# preamp_module_mic_rev1.net
KiCad netlist of a schematic drawn in EAGLE
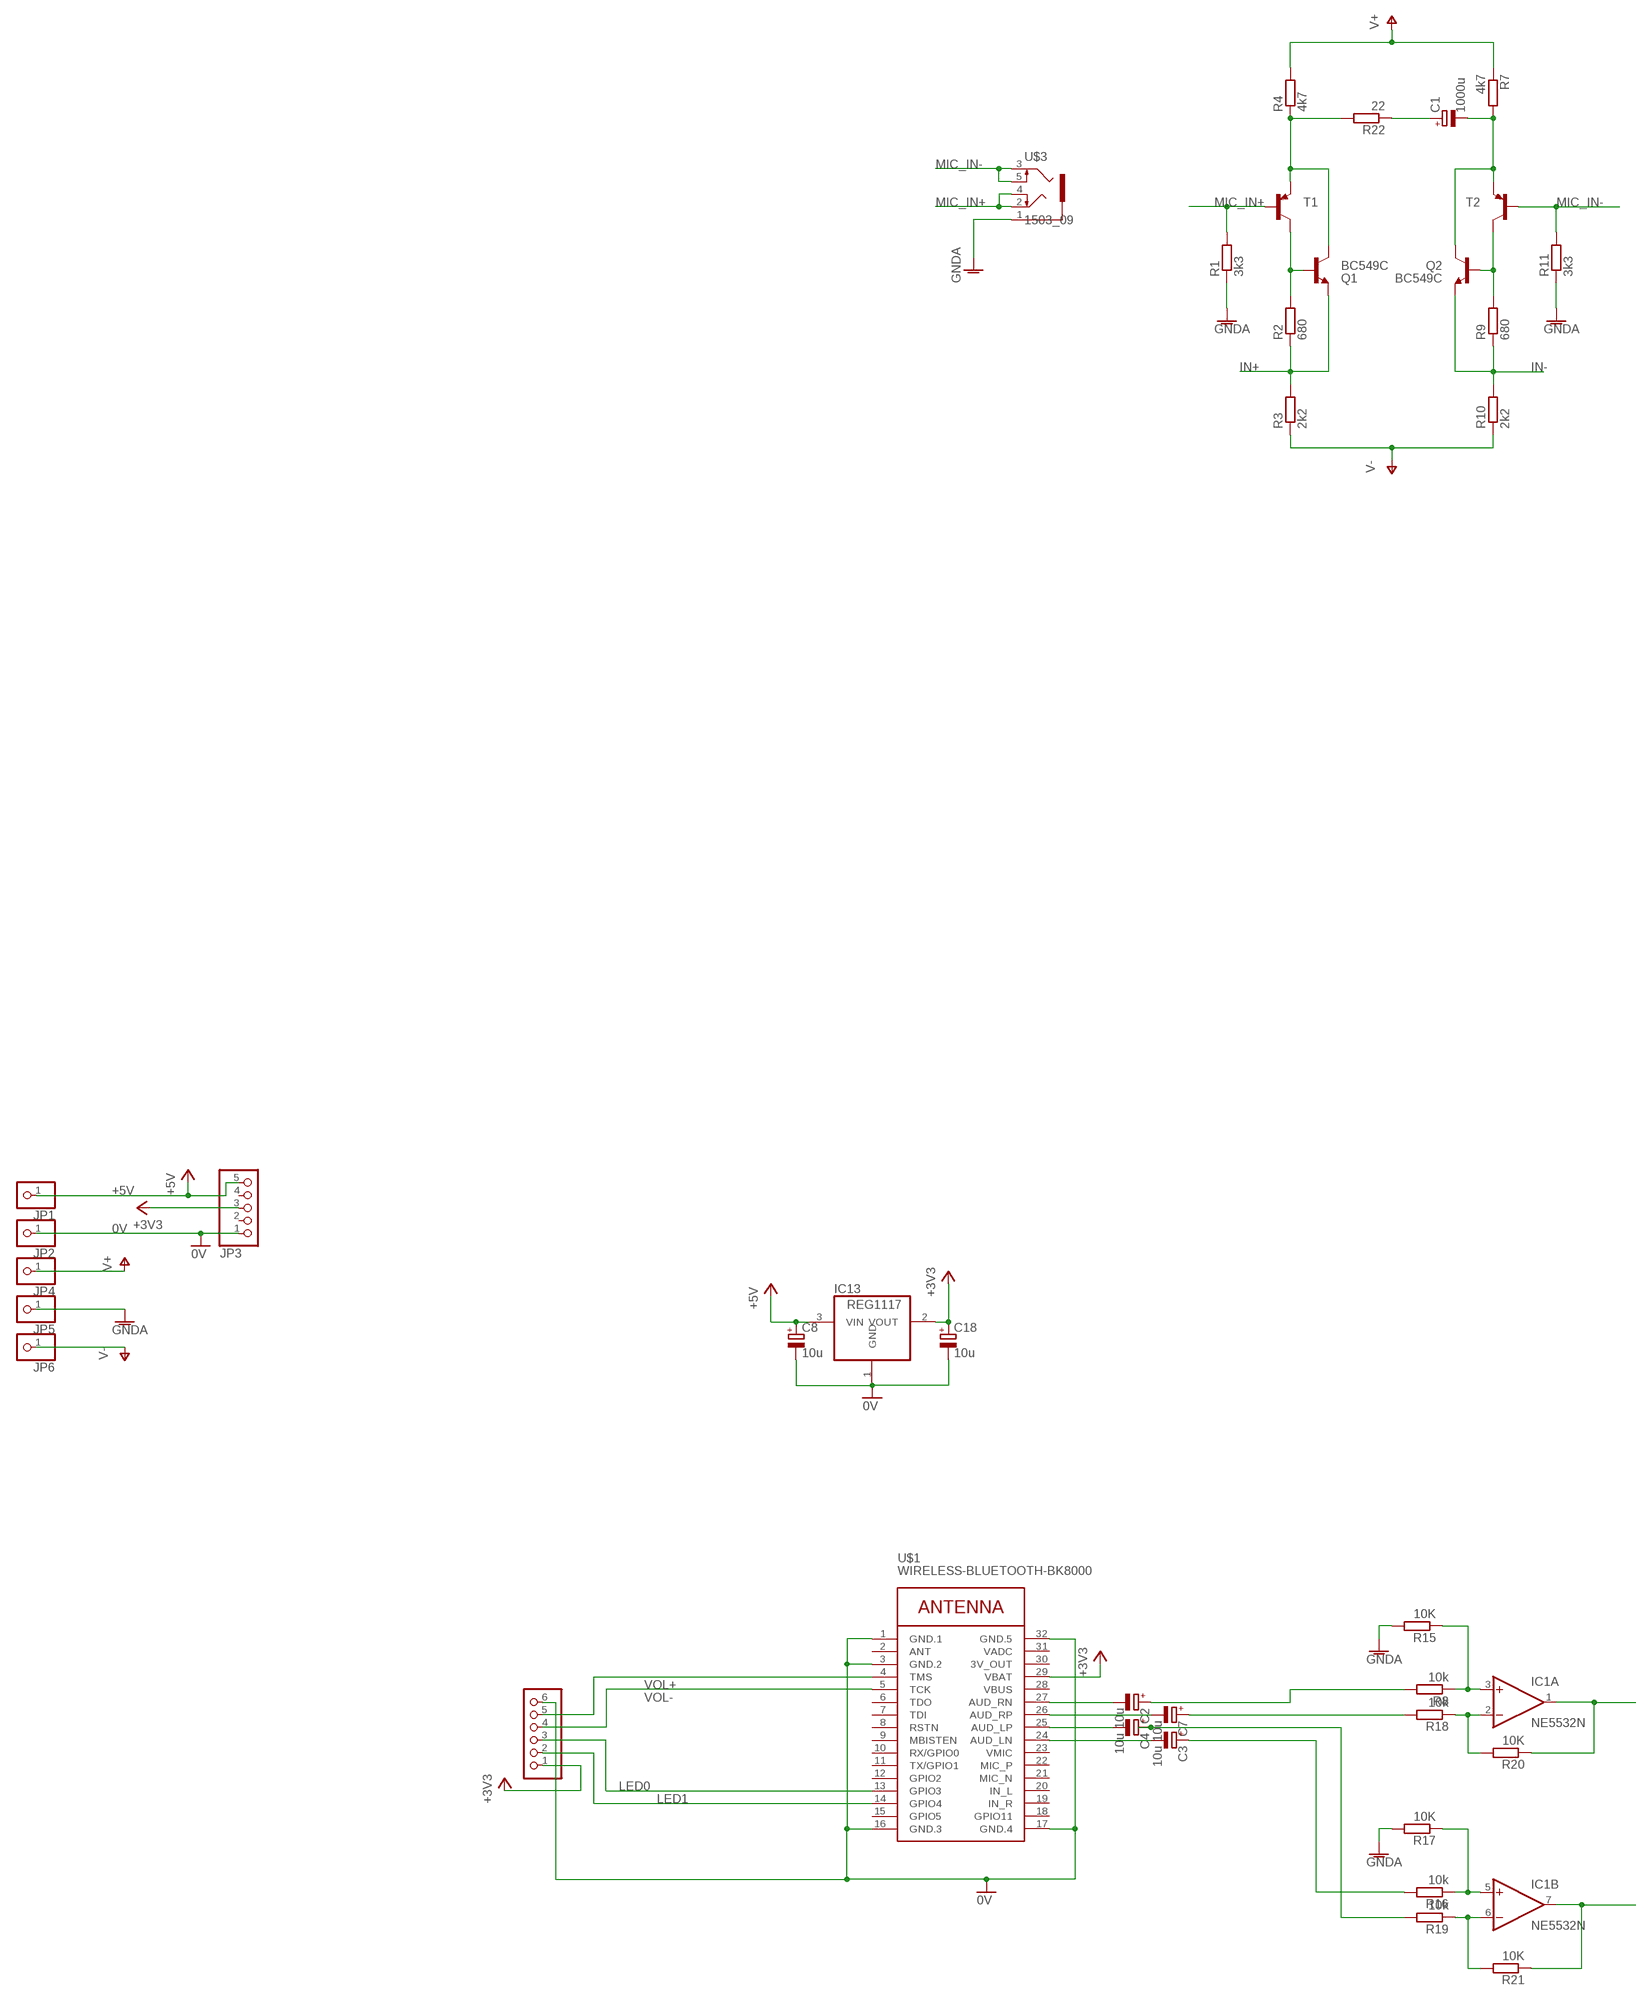
[diagram p0: schematic, sheet 1, part 1 of 2]
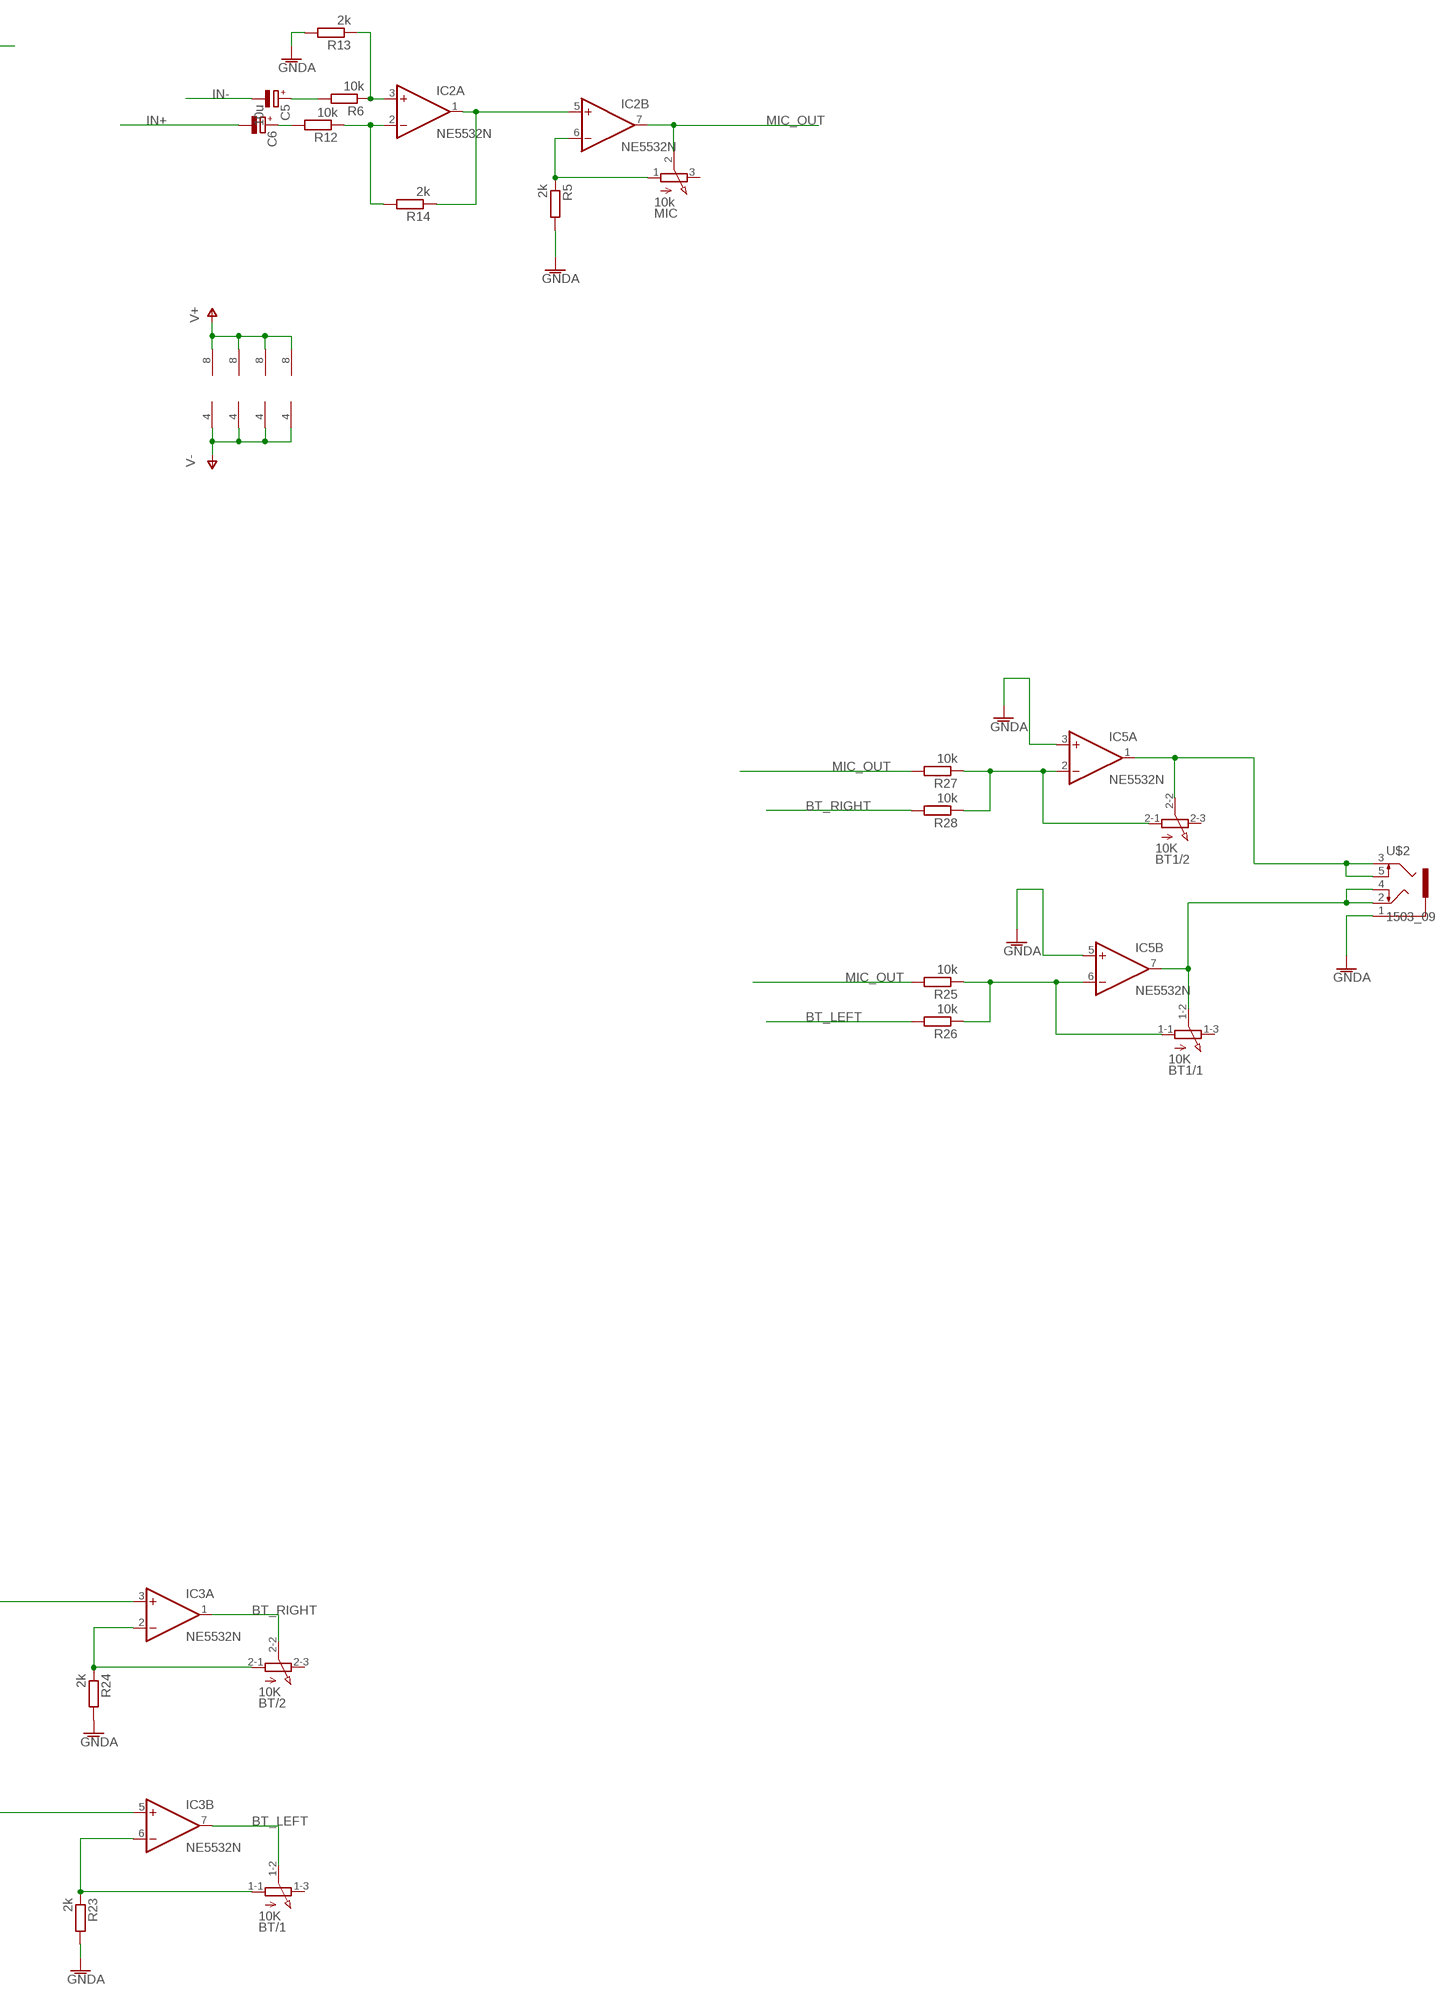
[diagram p1: schematic, sheet 1, part 2 of 2]

(export (version "E")
  (design (tool "Eeschema 10.0.6"))
  (components
    (comp (ref "BT")
      (value "10K")
      (footprint "eagle-import:3RP_1610G")
      (libsource (lib "eagle-import") (part "3RP/1610G"))
    )
    (comp (ref "BT1")
      (value "10K")
      (footprint "eagle-import:3RP_1610G")
      (libsource (lib "eagle-import") (part "3RP/1610G"))
    )
    (comp (ref "C1")
      (value "1000u")
      (footprint "eagle-import:E5-5")
      (libsource (lib "eagle-import") (part "CPOL-EUE5-5"))
    )
    (comp (ref "C2")
      (value "10u")
      (footprint "eagle-import:E2-5")
      (libsource (lib "eagle-import") (part "CPOL-EUE2-5"))
    )
    (comp (ref "C3")
      (value "10u")
      (footprint "eagle-import:E2-5")
      (libsource (lib "eagle-import") (part "CPOL-EUE2-5"))
    )
    (comp (ref "C4")
      (value "10u")
      (footprint "eagle-import:E2-5")
      (libsource (lib "eagle-import") (part "CPOL-EUE2-5"))
    )
    (comp (ref "C5")
      (value "10u")
      (footprint "eagle-import:E2-5")
      (libsource (lib "eagle-import") (part "CPOL-EUE2-5"))
    )
    (comp (ref "C6")
      (value "10u")
      (footprint "eagle-import:E2-5")
      (libsource (lib "eagle-import") (part "CPOL-EUE2-5"))
    )
    (comp (ref "C7")
      (value "10u")
      (footprint "eagle-import:E2-5")
      (libsource (lib "eagle-import") (part "CPOL-EUE2-5"))
    )
    (comp (ref "C8")
      (value "10u")
      (footprint "eagle-import:E2-5")
      (libsource (lib "eagle-import") (part "CPOL-EUE2-5"))
    )
    (comp (ref "C18")
      (value "10u")
      (footprint "eagle-import:E2-5")
      (libsource (lib "eagle-import") (part "CPOL-EUE2-5"))
    )
    (comp (ref "IC1")
      (value "NE5532N")
      (footprint "eagle-import:DIL08")
      (libsource (lib "eagle-import") (part "NE5532N"))
    )
    (comp (ref "IC2")
      (value "NE5532N")
      (footprint "eagle-import:DIL08")
      (libsource (lib "eagle-import") (part "NE5532N"))
    )
    (comp (ref "IC3")
      (value "NE5532N")
      (footprint "eagle-import:DIL08")
      (libsource (lib "eagle-import") (part "NE5532N"))
    )
    (comp (ref "IC5")
      (value "NE5532N")
      (footprint "eagle-import:DIL08")
      (libsource (lib "eagle-import") (part "NE5532N"))
    )
    (comp (ref "IC13")
      (value "REG1117")
      (footprint "eagle-import:SOT223")
      (libsource (lib "eagle-import") (part "REG1117"))
    )
    (comp (ref "JP1")
      (value "PINHD-1X1")
      (footprint "eagle-import:1X01")
      (libsource (lib "eagle-import") (part "PINHD-1X1"))
    )
    (comp (ref "JP2")
      (value "PINHD-1X1")
      (footprint "eagle-import:1X01")
      (libsource (lib "eagle-import") (part "PINHD-1X1"))
    )
    (comp (ref "JP3")
      (value "PINHD-1X5")
      (footprint "eagle-import:1X05")
      (libsource (lib "eagle-import") (part "PINHD-1X5"))
    )
    (comp (ref "JP4")
      (value "PINHD-1X1")
      (footprint "eagle-import:1X01")
      (libsource (lib "eagle-import") (part "PINHD-1X1"))
    )
    (comp (ref "JP5")
      (value "PINHD-1X1")
      (footprint "eagle-import:1X01")
      (libsource (lib "eagle-import") (part "PINHD-1X1"))
    )
    (comp (ref "JP6")
      (value "PINHD-1X1")
      (footprint "eagle-import:1X01")
      (libsource (lib "eagle-import") (part "PINHD-1X1"))
    )
    (comp (ref "JP7")
      (value "PINHD-1X6")
      (footprint "eagle-import:1X06")
      (libsource (lib "eagle-import") (part "PINHD-1X6"))
    )
    (comp (ref "MIC")
      (value "10k")
      (footprint "eagle-import:3RP_1610N")
      (libsource (lib "eagle-import") (part "3RP/1610N"))
    )
    (comp (ref "Q1")
      (value "BC549C")
      (footprint "eagle-import:TO92-EBC")
      (libsource (lib "eagle-import") (part "BC549C"))
    )
    (comp (ref "Q2")
      (value "BC549C")
      (footprint "eagle-import:TO92-EBC")
      (libsource (lib "eagle-import") (part "BC549C"))
    )
    (comp (ref "R1")
      (value "3k3")
      (footprint "eagle-import:0207_10")
      (libsource (lib "eagle-import") (part "R-EU_0207/10"))
    )
    (comp (ref "R2")
      (value "680")
      (footprint "eagle-import:0207_10")
      (libsource (lib "eagle-import") (part "R-EU_0207/10"))
    )
    (comp (ref "R3")
      (value "2k2")
      (footprint "eagle-import:0207_10")
      (libsource (lib "eagle-import") (part "R-EU_0207/10"))
    )
    (comp (ref "R4")
      (value "4k7")
      (footprint "eagle-import:0207_10")
      (libsource (lib "eagle-import") (part "R-EU_0207/10"))
    )
    (comp (ref "R5")
      (value "2k")
      (footprint "eagle-import:0207_10")
      (libsource (lib "eagle-import") (part "R-EU_0207/10"))
    )
    (comp (ref "R6")
      (value "10k")
      (footprint "eagle-import:0207_10")
      (libsource (lib "eagle-import") (part "R-EU_0207/10"))
    )
    (comp (ref "R7")
      (value "4k7")
      (footprint "eagle-import:0207_10")
      (libsource (lib "eagle-import") (part "R-EU_0207/10"))
    )
    (comp (ref "R8")
      (value "10k")
      (footprint "eagle-import:0207_10")
      (libsource (lib "eagle-import") (part "R-EU_0207/10"))
    )
    (comp (ref "R9")
      (value "680")
      (footprint "eagle-import:0207_10")
      (libsource (lib "eagle-import") (part "R-EU_0207/10"))
    )
    (comp (ref "R10")
      (value "2k2")
      (footprint "eagle-import:0207_10")
      (libsource (lib "eagle-import") (part "R-EU_0207/10"))
    )
    (comp (ref "R11")
      (value "3k3")
      (footprint "eagle-import:0207_10")
      (libsource (lib "eagle-import") (part "R-EU_0207/10"))
    )
    (comp (ref "R12")
      (value "10k")
      (footprint "eagle-import:0207_10")
      (libsource (lib "eagle-import") (part "R-EU_0207/10"))
    )
    (comp (ref "R13")
      (value "2k")
      (footprint "eagle-import:0207_10")
      (libsource (lib "eagle-import") (part "R-EU_0207/10"))
    )
    (comp (ref "R14")
      (value "2k")
      (footprint "eagle-import:0207_10")
      (libsource (lib "eagle-import") (part "R-EU_0207/10"))
    )
    (comp (ref "R15")
      (value "10K")
      (footprint "eagle-import:0207_10")
      (libsource (lib "eagle-import") (part "R-EU_0207/10"))
    )
    (comp (ref "R16")
      (value "10k")
      (footprint "eagle-import:0207_10")
      (libsource (lib "eagle-import") (part "R-EU_0207/10"))
    )
    (comp (ref "R17")
      (value "10K")
      (footprint "eagle-import:0207_10")
      (libsource (lib "eagle-import") (part "R-EU_0207/10"))
    )
    (comp (ref "R18")
      (value "10k")
      (footprint "eagle-import:0207_10")
      (libsource (lib "eagle-import") (part "R-EU_0207/10"))
    )
    (comp (ref "R19")
      (value "10k")
      (footprint "eagle-import:0207_10")
      (libsource (lib "eagle-import") (part "R-EU_0207/10"))
    )
    (comp (ref "R20")
      (value "10K")
      (footprint "eagle-import:0207_10")
      (libsource (lib "eagle-import") (part "R-EU_0207/10"))
    )
    (comp (ref "R21")
      (value "10K")
      (footprint "eagle-import:0207_10")
      (libsource (lib "eagle-import") (part "R-EU_0207/10"))
    )
    (comp (ref "R22")
      (value "22")
      (footprint "eagle-import:0207_10")
      (libsource (lib "eagle-import") (part "R-EU_0207/10"))
    )
    (comp (ref "R23")
      (value "2k")
      (footprint "eagle-import:0207_10")
      (libsource (lib "eagle-import") (part "R-EU_0207/10"))
    )
    (comp (ref "R24")
      (value "2k")
      (footprint "eagle-import:0207_10")
      (libsource (lib "eagle-import") (part "R-EU_0207/10"))
    )
    (comp (ref "R25")
      (value "10k")
      (footprint "eagle-import:0207_10")
      (libsource (lib "eagle-import") (part "R-EU_0207/10"))
    )
    (comp (ref "R26")
      (value "10k")
      (footprint "eagle-import:0207_10")
      (libsource (lib "eagle-import") (part "R-EU_0207/10"))
    )
    (comp (ref "R27")
      (value "10k")
      (footprint "eagle-import:0207_10")
      (libsource (lib "eagle-import") (part "R-EU_0207/10"))
    )
    (comp (ref "R28")
      (value "10k")
      (footprint "eagle-import:0207_10")
      (libsource (lib "eagle-import") (part "R-EU_0207/10"))
    )
    (comp (ref "T1")
      (value "2N4403-PNP-TO92-EBC")
      (footprint "eagle-import:TO92-EBC")
      (libsource (lib "eagle-import") (part "-PNP-TO92-EBC2N4403"))
    )
    (comp (ref "T2")
      (value "2N4403-PNP-TO92-EBC")
      (footprint "eagle-import:TO92-EBC")
      (libsource (lib "eagle-import") (part "-PNP-TO92-EBC2N4403"))
    )
    (comp (ref "U$1")
      (value "WIRELESS-BLUETOOTH-BK8000")
      (footprint "eagle-import:WIRELESS-BLUETOOTH-BK8000")
      (libsource (lib "eagle-import") (part "WIRELESS-BLUETOOTH-BK8000"))
    )
    (comp (ref "U$2")
      (value "1503_09")
      (footprint "eagle-import:1503_09")
      (libsource (lib "eagle-import") (part "1503_09"))
    )
    (comp (ref "U$3")
      (value "1503_09")
      (footprint "eagle-import:1503_09")
      (libsource (lib "eagle-import") (part "1503_09"))
    )
  )
  (nets
    (net (code "1") (name "+3V3") (class "Default")
      (node (ref "C18") (pin "+") (pinfunction "+_+") (pintype "passive"))
      (node (ref "IC13") (pin "2") (pinfunction "VOUT_2") (pintype "output"))
      (node (ref "JP3") (pin "3") (pinfunction "3_3") (pintype "passive"))
      (node (ref "JP7") (pin "1") (pinfunction "1_1") (pintype "passive"))
      (node (ref "U$1") (pin "29") (pinfunction "VBAT_29") (pintype "passive"))
    )
    (net (code "2") (name "+5V") (class "Default")
      (node (ref "C8") (pin "+") (pinfunction "+_+") (pintype "passive"))
      (node (ref "IC13") (pin "3") (pinfunction "VIN_3") (pintype "input"))
      (node (ref "JP1") (pin "1") (pinfunction "1_1") (pintype "passive"))
      (node (ref "JP3") (pin "5") (pinfunction "5_5") (pintype "passive"))
    )
    (net (code "3") (name "/3V_OUT") (class "Default")
      (node (ref "U$1") (pin "30") (pinfunction "3V_OUT_30") (pintype "power_in"))
    )
    (net (code "4") (name "/BT_LEFT") (class "Default")
      (node (ref "BT") (pin "1-2") (pinfunction "S_1-2") (pintype "passive"))
      (node (ref "IC3") (pin "7") (pinfunction "OUT_7") (pintype "output"))
      (node (ref "R26") (pin "2") (pinfunction "2_2") (pintype "passive"))
    )
    (net (code "5") (name "/BT_RIGHT") (class "Default")
      (node (ref "BT") (pin "2-2") (pinfunction "S_2-2") (pintype "passive"))
      (node (ref "IC3") (pin "1") (pinfunction "OUT_1") (pintype "output"))
      (node (ref "R28") (pin "2") (pinfunction "2_2") (pintype "passive"))
    )
    (net (code "6") (name "/IN+") (class "Default")
      (node (ref "C6") (pin "-") (pinfunction "-_-") (pintype "passive"))
      (node (ref "Q1") (pin "E") (pinfunction "E_E") (pintype "passive"))
      (node (ref "R2") (pin "1") (pinfunction "1_1") (pintype "passive"))
      (node (ref "R3") (pin "2") (pinfunction "2_2") (pintype "passive"))
    )
    (net (code "7") (name "/IN-") (class "Default")
      (node (ref "C5") (pin "-") (pinfunction "-_-") (pintype "passive"))
      (node (ref "Q2") (pin "E") (pinfunction "E_E") (pintype "passive"))
      (node (ref "R10") (pin "2") (pinfunction "2_2") (pintype "passive"))
      (node (ref "R9") (pin "1") (pinfunction "1_1") (pintype "passive"))
    )
    (net (code "8") (name "/LED0") (class "Default")
      (node (ref "JP7") (pin "3") (pinfunction "3_3") (pintype "passive"))
      (node (ref "U$1") (pin "13") (pinfunction "GPIO3_13") (pintype "bidirectional"))
    )
    (net (code "9") (name "/LED1") (class "Default")
      (node (ref "JP7") (pin "2") (pinfunction "2_2") (pintype "passive"))
      (node (ref "U$1") (pin "14") (pinfunction "GPIO4_14") (pintype "bidirectional"))
    )
    (net (code "10") (name "/MIC_IN+") (class "Default")
      (node (ref "R1") (pin "2") (pinfunction "2_2") (pintype "passive"))
      (node (ref "T1") (pin "B") (pinfunction "B_B") (pintype "passive"))
      (node (ref "U$3") (pin "2") (pinfunction "2_2") (pintype "passive"))
      (node (ref "U$3") (pin "4") (pinfunction "4_4") (pintype "passive"))
    )
    (net (code "11") (name "/MIC_IN-") (class "Default")
      (node (ref "R11") (pin "2") (pinfunction "2_2") (pintype "passive"))
      (node (ref "T2") (pin "B") (pinfunction "B_B") (pintype "passive"))
      (node (ref "U$3") (pin "3") (pinfunction "3_3") (pintype "passive"))
      (node (ref "U$3") (pin "5") (pinfunction "5_5") (pintype "passive"))
    )
    (net (code "12") (name "/MIC_OUT") (class "Default")
      (node (ref "IC2") (pin "7") (pinfunction "OUT_7") (pintype "output"))
      (node (ref "MIC") (pin "2") (pinfunction "S_2") (pintype "passive"))
      (node (ref "R25") (pin "2") (pinfunction "2_2") (pintype "passive"))
      (node (ref "R27") (pin "2") (pinfunction "2_2") (pintype "passive"))
    )
    (net (code "13") (name "/VADC") (class "Default")
      (node (ref "U$1") (pin "31") (pinfunction "VADC_31") (pintype "power_in"))
    )
    (net (code "14") (name "/VOL+") (class "Default")
      (node (ref "JP7") (pin "5") (pinfunction "5_5") (pintype "passive"))
      (node (ref "U$1") (pin "4") (pinfunction "TMS_4") (pintype "bidirectional"))
    )
    (net (code "15") (name "/VOL-") (class "Default")
      (node (ref "JP7") (pin "4") (pinfunction "4_4") (pintype "passive"))
      (node (ref "U$1") (pin "5") (pinfunction "TCK_5") (pintype "bidirectional"))
    )
    (net (code "16") (name "0V") (class "Default")
      (node (ref "C18") (pin "-") (pinfunction "-_-") (pintype "passive"))
      (node (ref "C8") (pin "-") (pinfunction "-_-") (pintype "passive"))
      (node (ref "IC13") (pin "1") (pinfunction "GND_1") (pintype "power_in"))
      (node (ref "JP2") (pin "1") (pinfunction "1_1") (pintype "passive"))
      (node (ref "JP3") (pin "1") (pinfunction "1_1") (pintype "passive"))
      (node (ref "JP7") (pin "6") (pinfunction "6_6") (pintype "passive"))
      (node (ref "U$1") (pin "1") (pinfunction "GND.1_1") (pintype "power_in"))
      (node (ref "U$1") (pin "16") (pinfunction "GND.3_16") (pintype "power_in"))
      (node (ref "U$1") (pin "17") (pinfunction "GND.4_17") (pintype "power_in"))
      (node (ref "U$1") (pin "3") (pinfunction "GND.2_3") (pintype "power_in"))
      (node (ref "U$1") (pin "32") (pinfunction "GND.5_32") (pintype "power_in"))
    )
    (net (code "17") (name "GNDA") (class "Default")
      (node (ref "IC5") (pin "3") (pinfunction "+IN_3") (pintype "input"))
      (node (ref "IC5") (pin "5") (pinfunction "+IN_5") (pintype "input"))
      (node (ref "JP5") (pin "1") (pinfunction "1_1") (pintype "passive"))
      (node (ref "R1") (pin "1") (pinfunction "1_1") (pintype "passive"))
      (node (ref "R11") (pin "1") (pinfunction "1_1") (pintype "passive"))
      (node (ref "R13") (pin "2") (pinfunction "2_2") (pintype "passive"))
      (node (ref "R15") (pin "2") (pinfunction "2_2") (pintype "passive"))
      (node (ref "R17") (pin "2") (pinfunction "2_2") (pintype "passive"))
      (node (ref "R23") (pin "2") (pinfunction "2_2") (pintype "passive"))
      (node (ref "R24") (pin "2") (pinfunction "2_2") (pintype "passive"))
      (node (ref "R5") (pin "2") (pinfunction "2_2") (pintype "passive"))
      (node (ref "U$2") (pin "1") (pinfunction "1_1") (pintype "passive"))
      (node (ref "U$3") (pin "1") (pinfunction "1_1") (pintype "passive"))
    )
    (net (code "18") (name "Net-(BT1A-A)") (class "Default")
      (node (ref "BT1") (pin "1-1") (pinfunction "A_1-1") (pintype "passive"))
      (node (ref "IC5") (pin "6") (pinfunction "-IN_6") (pintype "input"))
      (node (ref "R25") (pin "1") (pinfunction "1_1") (pintype "passive"))
      (node (ref "R26") (pin "1") (pinfunction "1_1") (pintype "passive"))
    )
    (net (code "19") (name "Net-(BT1A-S)") (class "Default")
      (node (ref "BT1") (pin "1-2") (pinfunction "S_1-2") (pintype "passive"))
      (node (ref "IC5") (pin "7") (pinfunction "OUT_7") (pintype "output"))
      (node (ref "U$2") (pin "2") (pinfunction "2_2") (pintype "passive"))
      (node (ref "U$2") (pin "4") (pinfunction "4_4") (pintype "passive"))
    )
    (net (code "20") (name "Net-(BT1B-A)") (class "Default")
      (node (ref "BT1") (pin "2-1") (pinfunction "A_2-1") (pintype "passive"))
      (node (ref "IC5") (pin "2") (pinfunction "-IN_2") (pintype "input"))
      (node (ref "R27") (pin "1") (pinfunction "1_1") (pintype "passive"))
      (node (ref "R28") (pin "1") (pinfunction "1_1") (pintype "passive"))
    )
    (net (code "21") (name "Net-(BT1B-S)") (class "Default")
      (node (ref "BT1") (pin "2-2") (pinfunction "S_2-2") (pintype "passive"))
      (node (ref "IC5") (pin "1") (pinfunction "OUT_1") (pintype "output"))
      (node (ref "U$2") (pin "3") (pinfunction "3_3") (pintype "passive"))
      (node (ref "U$2") (pin "5") (pinfunction "5_5") (pintype "passive"))
    )
    (net (code "22") (name "Net-(BTA-A)") (class "Default")
      (node (ref "BT") (pin "1-1") (pinfunction "A_1-1") (pintype "passive"))
      (node (ref "IC3") (pin "6") (pinfunction "-IN_6") (pintype "input"))
      (node (ref "R23") (pin "1") (pinfunction "1_1") (pintype "passive"))
    )
    (net (code "23") (name "Net-(BTB-A)") (class "Default")
      (node (ref "BT") (pin "2-1") (pinfunction "A_2-1") (pintype "passive"))
      (node (ref "IC3") (pin "2") (pinfunction "-IN_2") (pintype "input"))
      (node (ref "R24") (pin "1") (pinfunction "1_1") (pintype "passive"))
    )
    (net (code "24") (name "Net-(C1-Pad+)") (class "Default")
      (node (ref "C1") (pin "+") (pinfunction "+_+") (pintype "passive"))
      (node (ref "R22") (pin "1") (pinfunction "1_1") (pintype "passive"))
    )
    (net (code "25") (name "Net-(C1-Pad-)") (class "Default")
      (node (ref "C1") (pin "-") (pinfunction "-_-") (pintype "passive"))
      (node (ref "Q2") (pin "C") (pinfunction "C_C") (pintype "passive"))
      (node (ref "R7") (pin "2") (pinfunction "2_2") (pintype "passive"))
      (node (ref "T2") (pin "E") (pinfunction "E_E") (pintype "passive"))
    )
    (net (code "26") (name "Net-(C2-Pad+)") (class "Default")
      (node (ref "C2") (pin "+") (pinfunction "+_+") (pintype "passive"))
      (node (ref "R8") (pin "2") (pinfunction "2_2") (pintype "passive"))
    )
    (net (code "27") (name "Net-(C3-Pad+)") (class "Default")
      (node (ref "C3") (pin "+") (pinfunction "+_+") (pintype "passive"))
      (node (ref "R16") (pin "2") (pinfunction "2_2") (pintype "passive"))
    )
    (net (code "28") (name "Net-(C4-Pad+)") (class "Default")
      (node (ref "C4") (pin "+") (pinfunction "+_+") (pintype "passive"))
      (node (ref "R19") (pin "2") (pinfunction "2_2") (pintype "passive"))
    )
    (net (code "29") (name "Net-(C5-Pad+)") (class "Default")
      (node (ref "C5") (pin "+") (pinfunction "+_+") (pintype "passive"))
      (node (ref "R6") (pin "2") (pinfunction "2_2") (pintype "passive"))
    )
    (net (code "30") (name "Net-(C6-Pad+)") (class "Default")
      (node (ref "C6") (pin "+") (pinfunction "+_+") (pintype "passive"))
      (node (ref "R12") (pin "2") (pinfunction "2_2") (pintype "passive"))
    )
    (net (code "31") (name "Net-(C7-Pad+)") (class "Default")
      (node (ref "C7") (pin "+") (pinfunction "+_+") (pintype "passive"))
      (node (ref "R18") (pin "2") (pinfunction "2_2") (pintype "passive"))
    )
    (net (code "32") (name "Net-(IC1A-+IN)") (class "Default")
      (node (ref "IC1") (pin "3") (pinfunction "+IN_3") (pintype "input"))
      (node (ref "R15") (pin "1") (pinfunction "1_1") (pintype "passive"))
      (node (ref "R8") (pin "1") (pinfunction "1_1") (pintype "passive"))
    )
    (net (code "33") (name "Net-(IC1A--IN)") (class "Default")
      (node (ref "IC1") (pin "2") (pinfunction "-IN_2") (pintype "input"))
      (node (ref "R18") (pin "1") (pinfunction "1_1") (pintype "passive"))
      (node (ref "R20") (pin "2") (pinfunction "2_2") (pintype "passive"))
    )
    (net (code "34") (name "Net-(IC1A-OUT)") (class "Default")
      (node (ref "IC1") (pin "1") (pinfunction "OUT_1") (pintype "output"))
      (node (ref "IC3") (pin "3") (pinfunction "+IN_3") (pintype "input"))
      (node (ref "R20") (pin "1") (pinfunction "1_1") (pintype "passive"))
    )
    (net (code "35") (name "Net-(IC1B-+IN)") (class "Default")
      (node (ref "IC1") (pin "5") (pinfunction "+IN_5") (pintype "input"))
      (node (ref "R16") (pin "1") (pinfunction "1_1") (pintype "passive"))
      (node (ref "R17") (pin "1") (pinfunction "1_1") (pintype "passive"))
    )
    (net (code "36") (name "Net-(IC1B--IN)") (class "Default")
      (node (ref "IC1") (pin "6") (pinfunction "-IN_6") (pintype "input"))
      (node (ref "R19") (pin "1") (pinfunction "1_1") (pintype "passive"))
      (node (ref "R21") (pin "2") (pinfunction "2_2") (pintype "passive"))
    )
    (net (code "37") (name "Net-(IC1B-OUT)") (class "Default")
      (node (ref "IC1") (pin "7") (pinfunction "OUT_7") (pintype "output"))
      (node (ref "IC3") (pin "5") (pinfunction "+IN_5") (pintype "input"))
      (node (ref "R21") (pin "1") (pinfunction "1_1") (pintype "passive"))
    )
    (net (code "38") (name "Net-(IC2A-+IN)") (class "Default")
      (node (ref "IC2") (pin "3") (pinfunction "+IN_3") (pintype "input"))
      (node (ref "R13") (pin "1") (pinfunction "1_1") (pintype "passive"))
      (node (ref "R6") (pin "1") (pinfunction "1_1") (pintype "passive"))
    )
    (net (code "39") (name "Net-(IC2A--IN)") (class "Default")
      (node (ref "IC2") (pin "2") (pinfunction "-IN_2") (pintype "input"))
      (node (ref "R12") (pin "1") (pinfunction "1_1") (pintype "passive"))
      (node (ref "R14") (pin "2") (pinfunction "2_2") (pintype "passive"))
    )
    (net (code "40") (name "Net-(IC2A-OUT)") (class "Default")
      (node (ref "IC2") (pin "1") (pinfunction "OUT_1") (pintype "output"))
      (node (ref "IC2") (pin "5") (pinfunction "+IN_5") (pintype "input"))
      (node (ref "R14") (pin "1") (pinfunction "1_1") (pintype "passive"))
    )
    (net (code "41") (name "Net-(IC2B--IN)") (class "Default")
      (node (ref "IC2") (pin "6") (pinfunction "-IN_6") (pintype "input"))
      (node (ref "MIC") (pin "1") (pinfunction "A_1") (pintype "passive"))
      (node (ref "R5") (pin "1") (pinfunction "1_1") (pintype "passive"))
    )
    (net (code "42") (name "Net-(Q1-PadB)") (class "Default")
      (node (ref "Q1") (pin "B") (pinfunction "B_B") (pintype "passive"))
      (node (ref "R2") (pin "2") (pinfunction "2_2") (pintype "passive"))
      (node (ref "T1") (pin "C") (pinfunction "C_C") (pintype "passive"))
    )
    (net (code "43") (name "Net-(Q1-PadC)") (class "Default")
      (node (ref "Q1") (pin "C") (pinfunction "C_C") (pintype "passive"))
      (node (ref "R22") (pin "2") (pinfunction "2_2") (pintype "passive"))
      (node (ref "R4") (pin "1") (pinfunction "1_1") (pintype "passive"))
      (node (ref "T1") (pin "E") (pinfunction "E_E") (pintype "passive"))
    )
    (net (code "44") (name "Net-(Q2-PadB)") (class "Default")
      (node (ref "Q2") (pin "B") (pinfunction "B_B") (pintype "passive"))
      (node (ref "R9") (pin "2") (pinfunction "2_2") (pintype "passive"))
      (node (ref "T2") (pin "C") (pinfunction "C_C") (pintype "passive"))
    )
    (net (code "45") (name "Net-(U$1-AUD_LN)") (class "Default")
      (node (ref "C3") (pin "-") (pinfunction "-_-") (pintype "passive"))
      (node (ref "U$1") (pin "24") (pinfunction "AUD_LN_24") (pintype "output"))
    )
    (net (code "46") (name "Net-(U$1-AUD_LP)") (class "Default")
      (node (ref "C4") (pin "-") (pinfunction "-_-") (pintype "passive"))
      (node (ref "U$1") (pin "25") (pinfunction "AUD_LP_25") (pintype "output"))
    )
    (net (code "47") (name "Net-(U$1-AUD_RN)") (class "Default")
      (node (ref "C2") (pin "-") (pinfunction "-_-") (pintype "passive"))
      (node (ref "U$1") (pin "27") (pinfunction "AUD_RN_27") (pintype "output"))
    )
    (net (code "48") (name "Net-(U$1-AUD_RP)") (class "Default")
      (node (ref "C7") (pin "-") (pinfunction "-_-") (pintype "passive"))
      (node (ref "U$1") (pin "26") (pinfunction "AUD_RP_26") (pintype "output"))
    )
    (net (code "49") (name "V+") (class "Default")
      (node (ref "IC1") (pin "8") (pinfunction "V+_8") (pintype "power_in"))
      (node (ref "IC2") (pin "8") (pinfunction "V+_8") (pintype "power_in"))
      (node (ref "IC3") (pin "8") (pinfunction "V+_8") (pintype "power_in"))
      (node (ref "IC5") (pin "8") (pinfunction "V+_8") (pintype "power_in"))
      (node (ref "JP4") (pin "1") (pinfunction "1_1") (pintype "passive"))
      (node (ref "R4") (pin "2") (pinfunction "2_2") (pintype "passive"))
      (node (ref "R7") (pin "1") (pinfunction "1_1") (pintype "passive"))
    )
    (net (code "50") (name "V-") (class "Default")
      (node (ref "IC1") (pin "4") (pinfunction "V-_4") (pintype "power_in"))
      (node (ref "IC2") (pin "4") (pinfunction "V-_4") (pintype "power_in"))
      (node (ref "IC3") (pin "4") (pinfunction "V-_4") (pintype "power_in"))
      (node (ref "IC5") (pin "4") (pinfunction "V-_4") (pintype "power_in"))
      (node (ref "JP6") (pin "1") (pinfunction "1_1") (pintype "passive"))
      (node (ref "R10") (pin "1") (pinfunction "1_1") (pintype "passive"))
      (node (ref "R3") (pin "1") (pinfunction "1_1") (pintype "passive"))
    )
    (net (code "51") (name "unconnected-(BT1A-E-Pad1-3)") (class "Default")
      (node (ref "BT1") (pin "1-3") (pinfunction "E_1-3") (pintype "passive"))
    )
    (net (code "52") (name "unconnected-(BT1B-E-Pad2-3)") (class "Default")
      (node (ref "BT1") (pin "2-3") (pinfunction "E_2-3") (pintype "passive"))
    )
    (net (code "53") (name "unconnected-(BTA-E-Pad1-3)") (class "Default")
      (node (ref "BT") (pin "1-3") (pinfunction "E_1-3") (pintype "passive"))
    )
    (net (code "54") (name "unconnected-(BTB-E-Pad2-3)") (class "Default")
      (node (ref "BT") (pin "2-3") (pinfunction "E_2-3") (pintype "passive"))
    )
    (net (code "55") (name "unconnected-(JP3-Pad2)") (class "Default")
      (node (ref "JP3") (pin "2") (pinfunction "2_2") (pintype "passive"))
    )
    (net (code "56") (name "unconnected-(JP3-Pad4)") (class "Default")
      (node (ref "JP3") (pin "4") (pinfunction "4_4") (pintype "passive"))
    )
    (net (code "57") (name "unconnected-(MIC-E-Pad3)") (class "Default")
      (node (ref "MIC") (pin "3") (pinfunction "E_3") (pintype "passive"))
    )
    (net (code "58") (name "unconnected-(U$1-ANT-Pad2)") (class "Default")
      (node (ref "U$1") (pin "2") (pinfunction "ANT_2") (pintype "passive"))
    )
    (net (code "59") (name "unconnected-(U$1-GPIO2-Pad12)") (class "Default")
      (node (ref "U$1") (pin "12") (pinfunction "GPIO2_12") (pintype "bidirectional"))
    )
    (net (code "60") (name "unconnected-(U$1-GPIO5-Pad15)") (class "Default")
      (node (ref "U$1") (pin "15") (pinfunction "GPIO5_15") (pintype "bidirectional"))
    )
    (net (code "61") (name "unconnected-(U$1-GPIO11-Pad18)") (class "Default")
      (node (ref "U$1") (pin "18") (pinfunction "GPIO11_18") (pintype "bidirectional"))
    )
    (net (code "62") (name "unconnected-(U$1-IN_L-Pad20)") (class "Default")
      (node (ref "U$1") (pin "20") (pinfunction "IN_L_20") (pintype "input"))
    )
    (net (code "63") (name "unconnected-(U$1-IN_R-Pad19)") (class "Default")
      (node (ref "U$1") (pin "19") (pinfunction "IN_R_19") (pintype "input"))
    )
    (net (code "64") (name "unconnected-(U$1-MBISTEN-Pad9)") (class "Default")
      (node (ref "U$1") (pin "9") (pinfunction "MBISTEN_9") (pintype "bidirectional"))
    )
    (net (code "65") (name "unconnected-(U$1-MIC_N-Pad21)") (class "Default")
      (node (ref "U$1") (pin "21") (pinfunction "MIC_N_21") (pintype "input"))
    )
    (net (code "66") (name "unconnected-(U$1-MIC_P-Pad22)") (class "Default")
      (node (ref "U$1") (pin "22") (pinfunction "MIC_P_22") (pintype "input"))
    )
    (net (code "67") (name "unconnected-(U$1-RSTN-Pad8)") (class "Default")
      (node (ref "U$1") (pin "8") (pinfunction "RSTN_8") (pintype "bidirectional"))
    )
    (net (code "68") (name "unconnected-(U$1-RX{slash}GPIO0-Pad10)") (class "Default")
      (node (ref "U$1") (pin "10") (pinfunction "RX/GPIO0_10") (pintype "bidirectional"))
    )
    (net (code "69") (name "unconnected-(U$1-TDI-Pad7)") (class "Default")
      (node (ref "U$1") (pin "7") (pinfunction "TDI_7") (pintype "bidirectional"))
    )
    (net (code "70") (name "unconnected-(U$1-TDO-Pad6)") (class "Default")
      (node (ref "U$1") (pin "6") (pinfunction "TDO_6") (pintype "bidirectional"))
    )
    (net (code "71") (name "unconnected-(U$1-TX{slash}GPIO1-Pad11)") (class "Default")
      (node (ref "U$1") (pin "11") (pinfunction "TX/GPIO1_11") (pintype "bidirectional"))
    )
    (net (code "72") (name "unconnected-(U$1-VBUS-Pad28)") (class "Default")
      (node (ref "U$1") (pin "28") (pinfunction "VBUS_28") (pintype "passive"))
    )
    (net (code "73") (name "unconnected-(U$1-VMIC-Pad23)") (class "Default")
      (node (ref "U$1") (pin "23") (pinfunction "VMIC_23") (pintype "passive"))
    )
  )
)
